# MCP23017_I8O4_v1_1.net
KiCad netlist of a schematic drawn in EAGLE
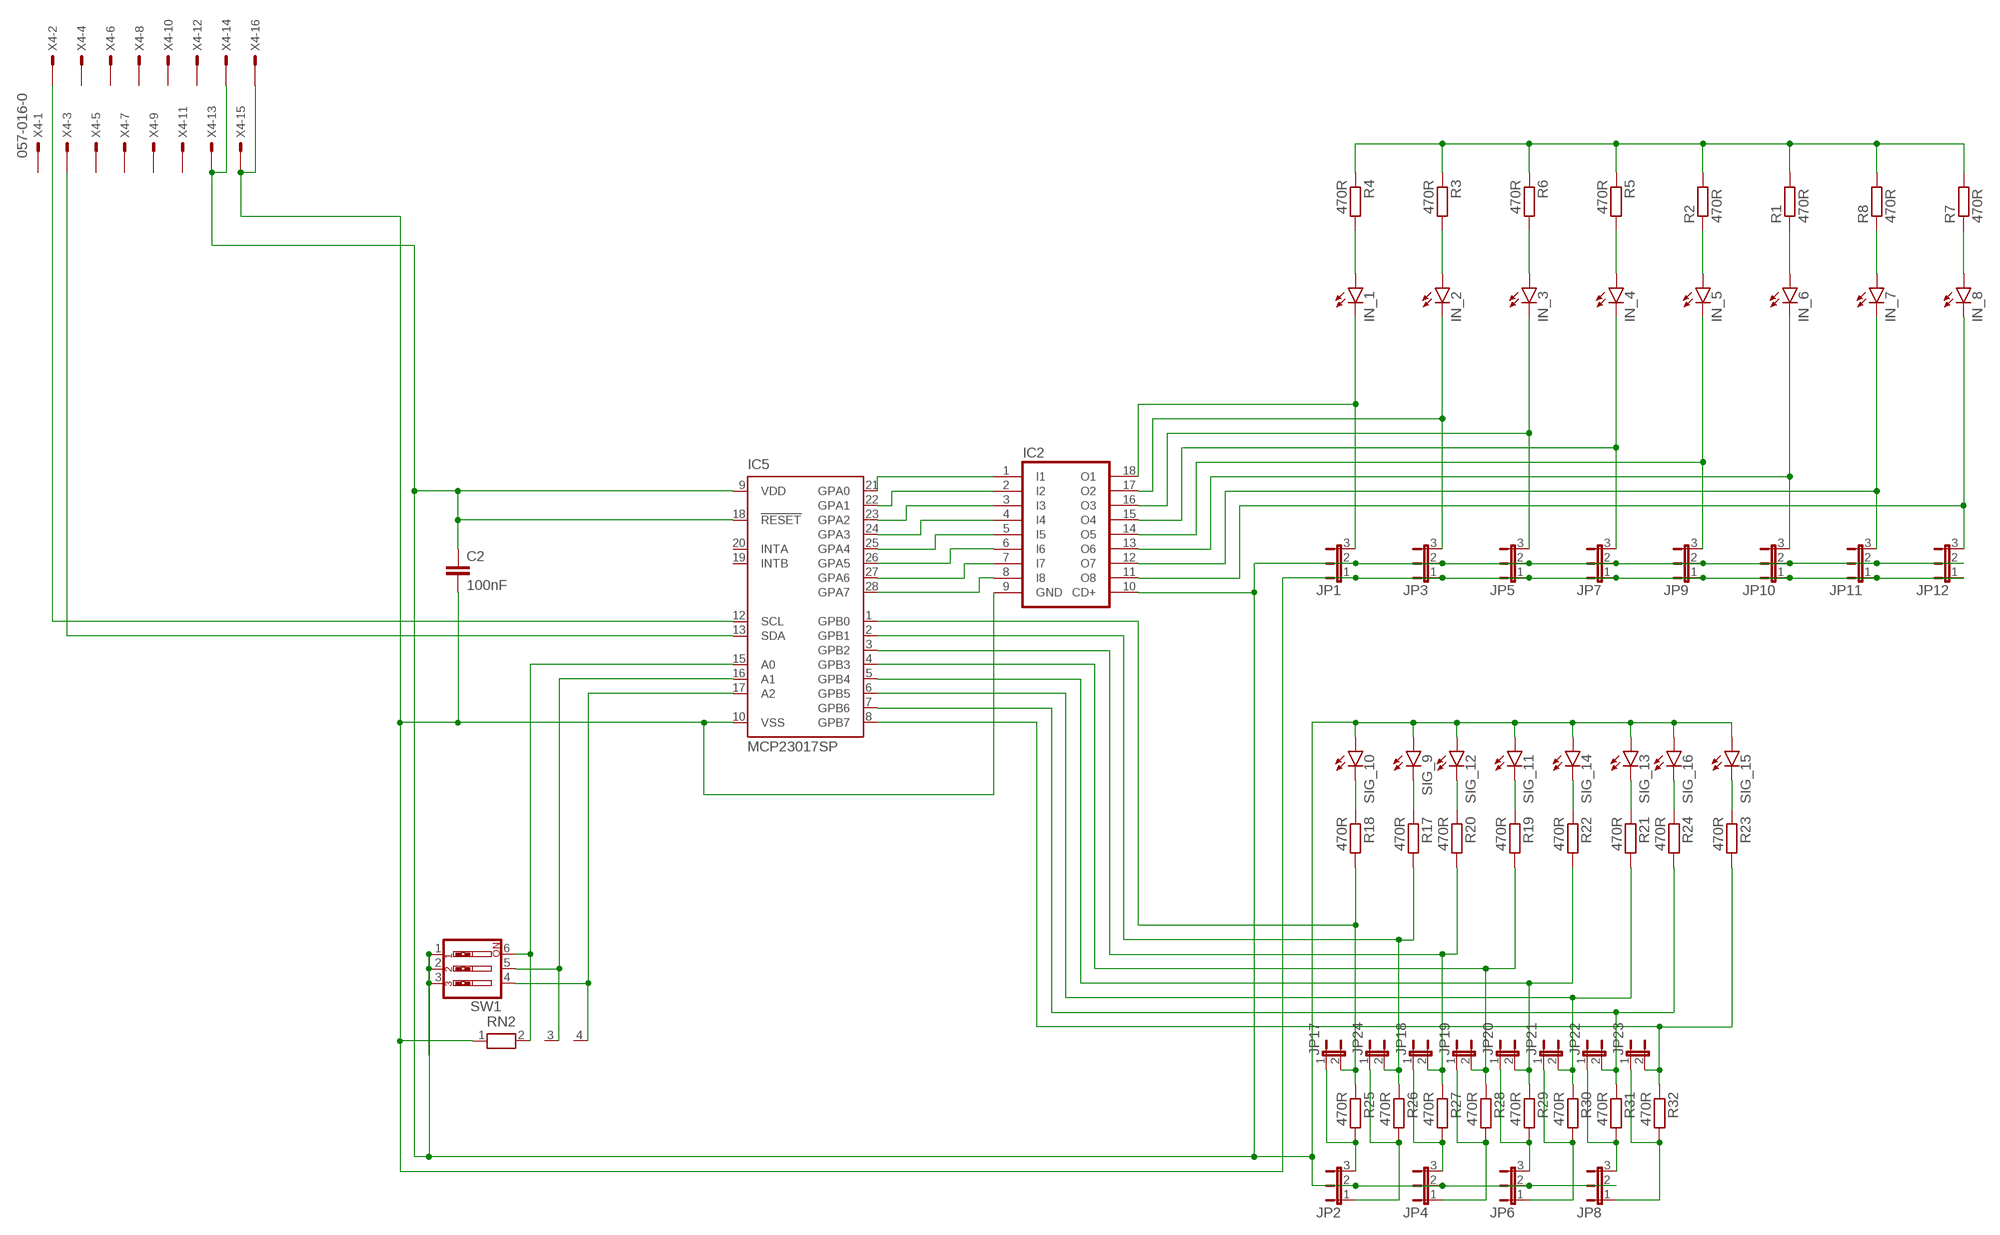
[diagram p0: schematic, sheet 1]

(export (version "E")
  (design (tool "Eeschema 10.0.6"))
  (components
    (comp (ref "C2")
      (value "100nF")
      (footprint "eagle-import:C025-024X044")
      (libsource (lib "eagle-import") (part "C-EU025-024X044"))
    )
    (comp (ref "IC2")
      (value "ULN2803A")
      (footprint "eagle-import:DIL18")
      (libsource (lib "eagle-import") (part "ULN2803A"))
    )
    (comp (ref "IC5")
      (value "MCP23017SP")
      (footprint "eagle-import:DIL28-3")
      (libsource (lib "eagle-import") (part "MCP23017SP"))
    )
    (comp (ref "IN_1")
      (value "LED3MM")
      (footprint "eagle-import:LED3MM")
      (libsource (lib "eagle-import") (part "LED3MM"))
    )
    (comp (ref "IN_2")
      (value "LED3MM")
      (footprint "eagle-import:LED3MM")
      (libsource (lib "eagle-import") (part "LED3MM"))
    )
    (comp (ref "IN_3")
      (value "LED3MM")
      (footprint "eagle-import:LED3MM")
      (libsource (lib "eagle-import") (part "LED3MM"))
    )
    (comp (ref "IN_4")
      (value "LED3MM")
      (footprint "eagle-import:LED3MM")
      (libsource (lib "eagle-import") (part "LED3MM"))
    )
    (comp (ref "IN_5")
      (value "LED3MM")
      (footprint "eagle-import:LED3MM")
      (libsource (lib "eagle-import") (part "LED3MM"))
    )
    (comp (ref "IN_6")
      (value "LED3MM")
      (footprint "eagle-import:LED3MM")
      (libsource (lib "eagle-import") (part "LED3MM"))
    )
    (comp (ref "IN_7")
      (value "LED3MM")
      (footprint "eagle-import:LED3MM")
      (libsource (lib "eagle-import") (part "LED3MM"))
    )
    (comp (ref "IN_8")
      (value "LED3MM")
      (footprint "eagle-import:LED3MM")
      (libsource (lib "eagle-import") (part "LED3MM"))
    )
    (comp (ref "JP1")
      (value "JP2E")
      (footprint "eagle-import:JP2")
      (libsource (lib "eagle-import") (part "JP2E"))
    )
    (comp (ref "JP2")
      (value "JP2E")
      (footprint "eagle-import:JP2")
      (libsource (lib "eagle-import") (part "JP2E"))
    )
    (comp (ref "JP3")
      (value "JP2E")
      (footprint "eagle-import:JP2")
      (libsource (lib "eagle-import") (part "JP2E"))
    )
    (comp (ref "JP4")
      (value "JP2E")
      (footprint "eagle-import:JP2")
      (libsource (lib "eagle-import") (part "JP2E"))
    )
    (comp (ref "JP5")
      (value "JP2E")
      (footprint "eagle-import:JP2")
      (libsource (lib "eagle-import") (part "JP2E"))
    )
    (comp (ref "JP6")
      (value "JP2E")
      (footprint "eagle-import:JP2")
      (libsource (lib "eagle-import") (part "JP2E"))
    )
    (comp (ref "JP7")
      (value "JP2E")
      (footprint "eagle-import:JP2")
      (libsource (lib "eagle-import") (part "JP2E"))
    )
    (comp (ref "JP8")
      (value "JP2E")
      (footprint "eagle-import:JP2")
      (libsource (lib "eagle-import") (part "JP2E"))
    )
    (comp (ref "JP9")
      (value "JP2E")
      (footprint "eagle-import:JP2")
      (libsource (lib "eagle-import") (part "JP2E"))
    )
    (comp (ref "JP10")
      (value "JP2E")
      (footprint "eagle-import:JP2")
      (libsource (lib "eagle-import") (part "JP2E"))
    )
    (comp (ref "JP11")
      (value "JP2E")
      (footprint "eagle-import:JP2")
      (libsource (lib "eagle-import") (part "JP2E"))
    )
    (comp (ref "JP12")
      (value "JP2E")
      (footprint "eagle-import:JP2")
      (libsource (lib "eagle-import") (part "JP2E"))
    )
    (comp (ref "JP17")
      (value "JP1E")
      (footprint "eagle-import:JP1")
      (libsource (lib "eagle-import") (part "JP1E"))
    )
    (comp (ref "JP18")
      (value "JP1E")
      (footprint "eagle-import:JP1")
      (libsource (lib "eagle-import") (part "JP1E"))
    )
    (comp (ref "JP19")
      (value "JP1E")
      (footprint "eagle-import:JP1")
      (libsource (lib "eagle-import") (part "JP1E"))
    )
    (comp (ref "JP20")
      (value "JP1E")
      (footprint "eagle-import:JP1")
      (libsource (lib "eagle-import") (part "JP1E"))
    )
    (comp (ref "JP21")
      (value "JP1E")
      (footprint "eagle-import:JP1")
      (libsource (lib "eagle-import") (part "JP1E"))
    )
    (comp (ref "JP22")
      (value "JP1E")
      (footprint "eagle-import:JP1")
      (libsource (lib "eagle-import") (part "JP1E"))
    )
    (comp (ref "JP23")
      (value "JP1E")
      (footprint "eagle-import:JP1")
      (libsource (lib "eagle-import") (part "JP1E"))
    )
    (comp (ref "JP24")
      (value "JP1E")
      (footprint "eagle-import:JP1")
      (libsource (lib "eagle-import") (part "JP1E"))
    )
    (comp (ref "R1")
      (value "470R")
      (footprint "eagle-import:0309_10")
      (libsource (lib "eagle-import") (part "R-EU_0309/10"))
    )
    (comp (ref "R2")
      (value "470R")
      (footprint "eagle-import:0309_10")
      (libsource (lib "eagle-import") (part "R-EU_0309/10"))
    )
    (comp (ref "R3")
      (value "470R")
      (footprint "eagle-import:0309_10")
      (libsource (lib "eagle-import") (part "R-EU_0309/10"))
    )
    (comp (ref "R4")
      (value "470R")
      (footprint "eagle-import:0309_10")
      (libsource (lib "eagle-import") (part "R-EU_0309/10"))
    )
    (comp (ref "R5")
      (value "470R")
      (footprint "eagle-import:0309_10")
      (libsource (lib "eagle-import") (part "R-EU_0309/10"))
    )
    (comp (ref "R6")
      (value "470R")
      (footprint "eagle-import:0309_10")
      (libsource (lib "eagle-import") (part "R-EU_0309/10"))
    )
    (comp (ref "R7")
      (value "470R")
      (footprint "eagle-import:0309_10")
      (libsource (lib "eagle-import") (part "R-EU_0309/10"))
    )
    (comp (ref "R8")
      (value "470R")
      (footprint "eagle-import:0309_10")
      (libsource (lib "eagle-import") (part "R-EU_0309/10"))
    )
    (comp (ref "R17")
      (value "470R")
      (footprint "eagle-import:0309_10")
      (libsource (lib "eagle-import") (part "R-EU_0309/10"))
    )
    (comp (ref "R18")
      (value "470R")
      (footprint "eagle-import:0309_10")
      (libsource (lib "eagle-import") (part "R-EU_0309/10"))
    )
    (comp (ref "R19")
      (value "470R")
      (footprint "eagle-import:0309_10")
      (libsource (lib "eagle-import") (part "R-EU_0309/10"))
    )
    (comp (ref "R20")
      (value "470R")
      (footprint "eagle-import:0309_10")
      (libsource (lib "eagle-import") (part "R-EU_0309/10"))
    )
    (comp (ref "R21")
      (value "470R")
      (footprint "eagle-import:0309_10")
      (libsource (lib "eagle-import") (part "R-EU_0309/10"))
    )
    (comp (ref "R22")
      (value "470R")
      (footprint "eagle-import:0309_10")
      (libsource (lib "eagle-import") (part "R-EU_0309/10"))
    )
    (comp (ref "R23")
      (value "470R")
      (footprint "eagle-import:0309_10")
      (libsource (lib "eagle-import") (part "R-EU_0309/10"))
    )
    (comp (ref "R24")
      (value "470R")
      (footprint "eagle-import:0309_10")
      (libsource (lib "eagle-import") (part "R-EU_0309/10"))
    )
    (comp (ref "R25")
      (value "470R")
      (footprint "eagle-import:0309_10")
      (libsource (lib "eagle-import") (part "R-EU_0309/10"))
    )
    (comp (ref "R26")
      (value "470R")
      (footprint "eagle-import:0309_10")
      (libsource (lib "eagle-import") (part "R-EU_0309/10"))
    )
    (comp (ref "R27")
      (value "470R")
      (footprint "eagle-import:0309_10")
      (libsource (lib "eagle-import") (part "R-EU_0309/10"))
    )
    (comp (ref "R28")
      (value "470R")
      (footprint "eagle-import:0309_10")
      (libsource (lib "eagle-import") (part "R-EU_0309/10"))
    )
    (comp (ref "R29")
      (value "470R")
      (footprint "eagle-import:0309_10")
      (libsource (lib "eagle-import") (part "R-EU_0309/10"))
    )
    (comp (ref "R30")
      (value "470R")
      (footprint "eagle-import:0309_10")
      (libsource (lib "eagle-import") (part "R-EU_0309/10"))
    )
    (comp (ref "R31")
      (value "470R")
      (footprint "eagle-import:0309_10")
      (libsource (lib "eagle-import") (part "R-EU_0309/10"))
    )
    (comp (ref "R32")
      (value "470R")
      (footprint "eagle-import:0309_10")
      (libsource (lib "eagle-import") (part "R-EU_0309/10"))
    )
    (comp (ref "RN2")
      (value "RN03")
      (footprint "eagle-import:RN-3")
      (libsource (lib "eagle-import") (part "RN03"))
    )
    (comp (ref "SIG_9")
      (value "LED3MM")
      (footprint "eagle-import:LED3MM")
      (libsource (lib "eagle-import") (part "LED3MM"))
    )
    (comp (ref "SIG_10")
      (value "LED3MM")
      (footprint "eagle-import:LED3MM")
      (libsource (lib "eagle-import") (part "LED3MM"))
    )
    (comp (ref "SIG_11")
      (value "LED3MM")
      (footprint "eagle-import:LED3MM")
      (libsource (lib "eagle-import") (part "LED3MM"))
    )
    (comp (ref "SIG_12")
      (value "LED3MM")
      (footprint "eagle-import:LED3MM")
      (libsource (lib "eagle-import") (part "LED3MM"))
    )
    (comp (ref "SIG_13")
      (value "LED3MM")
      (footprint "eagle-import:LED3MM")
      (libsource (lib "eagle-import") (part "LED3MM"))
    )
    (comp (ref "SIG_14")
      (value "LED3MM")
      (footprint "eagle-import:LED3MM")
      (libsource (lib "eagle-import") (part "LED3MM"))
    )
    (comp (ref "SIG_15")
      (value "LED3MM")
      (footprint "eagle-import:LED3MM")
      (libsource (lib "eagle-import") (part "LED3MM"))
    )
    (comp (ref "SIG_16")
      (value "LED3MM")
      (footprint "eagle-import:LED3MM")
      (libsource (lib "eagle-import") (part "LED3MM"))
    )
    (comp (ref "SW1")
      (value "SW_DIP-3")
      (footprint "eagle-import:EDG-03")
      (libsource (lib "eagle-import") (part "SW_DIP-3"))
    )
    (comp (ref "X4")
      (value "057-016-0")
      (footprint "eagle-import:057-016-0")
      (libsource (lib "eagle-import") (part "057-016-0"))
    )
  )
  (nets
    (net (code "1") (name "Net-(IC2-CD+)") (class "Default")
      (node (ref "C2") (pin "1") (pinfunction "1_1") (pintype "passive"))
      (node (ref "IC2") (pin "10") (pinfunction "CD+_10") (pintype "passive"))
      (node (ref "IC5") (pin "18") (pinfunction "~{RESET}_18") (pintype "input"))
      (node (ref "IC5") (pin "9") (pinfunction "VDD_9") (pintype "power_in"))
      (node (ref "JP1") (pin "2") (pinfunction "2_2") (pintype "passive"))
      (node (ref "JP10") (pin "2") (pinfunction "2_2") (pintype "passive"))
      (node (ref "JP11") (pin "2") (pinfunction "2_2") (pintype "passive"))
      (node (ref "JP12") (pin "2") (pinfunction "2_2") (pintype "passive"))
      (node (ref "JP2") (pin "2") (pinfunction "2_2") (pintype "passive"))
      (node (ref "JP3") (pin "2") (pinfunction "2_2") (pintype "passive"))
      (node (ref "JP4") (pin "2") (pinfunction "2_2") (pintype "passive"))
      (node (ref "JP5") (pin "2") (pinfunction "2_2") (pintype "passive"))
      (node (ref "JP6") (pin "2") (pinfunction "2_2") (pintype "passive"))
      (node (ref "JP7") (pin "2") (pinfunction "2_2") (pintype "passive"))
      (node (ref "JP8") (pin "2") (pinfunction "2_2") (pintype "passive"))
      (node (ref "JP9") (pin "2") (pinfunction "2_2") (pintype "passive"))
      (node (ref "SIG_10") (pin "A") (pinfunction "A_A") (pintype "passive"))
      (node (ref "SIG_11") (pin "A") (pinfunction "A_A") (pintype "passive"))
      (node (ref "SIG_12") (pin "A") (pinfunction "A_A") (pintype "passive"))
      (node (ref "SIG_13") (pin "A") (pinfunction "A_A") (pintype "passive"))
      (node (ref "SIG_14") (pin "A") (pinfunction "A_A") (pintype "passive"))
      (node (ref "SIG_15") (pin "A") (pinfunction "A_A") (pintype "passive"))
      (node (ref "SIG_16") (pin "A") (pinfunction "A_A") (pintype "passive"))
      (node (ref "SIG_9") (pin "A") (pinfunction "A_A") (pintype "passive"))
      (node (ref "SW1") (pin "1") (pinfunction "1_1") (pintype "passive"))
      (node (ref "SW1") (pin "2") (pinfunction "2_2") (pintype "passive"))
      (node (ref "SW1") (pin "3") (pinfunction "3_3") (pintype "passive"))
      (node (ref "X4") (pin "13") (pinfunction "S_13") (pintype "passive"))
      (node (ref "X4") (pin "14") (pinfunction "S_14") (pintype "passive"))
    )
    (net (code "2") (name "Net-(IC2-GND)") (class "Default")
      (node (ref "C2") (pin "2") (pinfunction "2_2") (pintype "passive"))
      (node (ref "IC2") (pin "9") (pinfunction "GND_9") (pintype "power_in"))
      (node (ref "IC5") (pin "10") (pinfunction "VSS_10") (pintype "power_in"))
      (node (ref "JP1") (pin "1") (pinfunction "1_1") (pintype "passive"))
      (node (ref "JP10") (pin "1") (pinfunction "1_1") (pintype "passive"))
      (node (ref "JP11") (pin "1") (pinfunction "1_1") (pintype "passive"))
      (node (ref "JP12") (pin "1") (pinfunction "1_1") (pintype "passive"))
      (node (ref "JP3") (pin "1") (pinfunction "1_1") (pintype "passive"))
      (node (ref "JP5") (pin "1") (pinfunction "1_1") (pintype "passive"))
      (node (ref "JP7") (pin "1") (pinfunction "1_1") (pintype "passive"))
      (node (ref "JP9") (pin "1") (pinfunction "1_1") (pintype "passive"))
      (node (ref "RN2") (pin "1") (pinfunction "1_1") (pintype "passive"))
      (node (ref "X4") (pin "15") (pinfunction "S_15") (pintype "passive"))
      (node (ref "X4") (pin "16") (pinfunction "S_16") (pintype "passive"))
    )
    (net (code "3") (name "Net-(IC2-I1)") (class "Default")
      (node (ref "IC2") (pin "1") (pinfunction "I1_1") (pintype "input"))
      (node (ref "IC5") (pin "21") (pinfunction "GPA0_21") (pintype "bidirectional"))
    )
    (net (code "4") (name "Net-(IC2-I2)") (class "Default")
      (node (ref "IC2") (pin "2") (pinfunction "I2_2") (pintype "input"))
      (node (ref "IC5") (pin "22") (pinfunction "GPA1_22") (pintype "bidirectional"))
    )
    (net (code "5") (name "Net-(IC2-I3)") (class "Default")
      (node (ref "IC2") (pin "3") (pinfunction "I3_3") (pintype "input"))
      (node (ref "IC5") (pin "23") (pinfunction "GPA2_23") (pintype "bidirectional"))
    )
    (net (code "6") (name "Net-(IC2-I4)") (class "Default")
      (node (ref "IC2") (pin "4") (pinfunction "I4_4") (pintype "input"))
      (node (ref "IC5") (pin "24") (pinfunction "GPA3_24") (pintype "bidirectional"))
    )
    (net (code "7") (name "Net-(IC2-I5)") (class "Default")
      (node (ref "IC2") (pin "5") (pinfunction "I5_5") (pintype "input"))
      (node (ref "IC5") (pin "25") (pinfunction "GPA4_25") (pintype "bidirectional"))
    )
    (net (code "8") (name "Net-(IC2-I6)") (class "Default")
      (node (ref "IC2") (pin "6") (pinfunction "I6_6") (pintype "input"))
      (node (ref "IC5") (pin "26") (pinfunction "GPA5_26") (pintype "bidirectional"))
    )
    (net (code "9") (name "Net-(IC2-I7)") (class "Default")
      (node (ref "IC2") (pin "7") (pinfunction "I7_7") (pintype "input"))
      (node (ref "IC5") (pin "27") (pinfunction "GPA6_27") (pintype "bidirectional"))
    )
    (net (code "10") (name "Net-(IC2-I8)") (class "Default")
      (node (ref "IC2") (pin "8") (pinfunction "I8_8") (pintype "input"))
      (node (ref "IC5") (pin "28") (pinfunction "GPA7_28") (pintype "bidirectional"))
    )
    (net (code "11") (name "Net-(IC2-O1)") (class "Default")
      (node (ref "IC2") (pin "18") (pinfunction "O1_18") (pintype "open_collector"))
      (node (ref "IN_1") (pin "K") (pinfunction "C_K") (pintype "passive"))
      (node (ref "JP1") (pin "3") (pinfunction "3_3") (pintype "passive"))
    )
    (net (code "12") (name "Net-(IC2-O2)") (class "Default")
      (node (ref "IC2") (pin "17") (pinfunction "O2_17") (pintype "open_collector"))
      (node (ref "IN_2") (pin "K") (pinfunction "C_K") (pintype "passive"))
      (node (ref "JP3") (pin "3") (pinfunction "3_3") (pintype "passive"))
    )
    (net (code "13") (name "Net-(IC2-O3)") (class "Default")
      (node (ref "IC2") (pin "16") (pinfunction "O3_16") (pintype "open_collector"))
      (node (ref "IN_3") (pin "K") (pinfunction "C_K") (pintype "passive"))
      (node (ref "JP5") (pin "3") (pinfunction "3_3") (pintype "passive"))
    )
    (net (code "14") (name "Net-(IC2-O4)") (class "Default")
      (node (ref "IC2") (pin "15") (pinfunction "O4_15") (pintype "open_collector"))
      (node (ref "IN_4") (pin "K") (pinfunction "C_K") (pintype "passive"))
      (node (ref "JP7") (pin "3") (pinfunction "3_3") (pintype "passive"))
    )
    (net (code "15") (name "Net-(IC2-O5)") (class "Default")
      (node (ref "IC2") (pin "14") (pinfunction "O5_14") (pintype "open_collector"))
      (node (ref "IN_5") (pin "K") (pinfunction "C_K") (pintype "passive"))
      (node (ref "JP9") (pin "3") (pinfunction "3_3") (pintype "passive"))
    )
    (net (code "16") (name "Net-(IC2-O6)") (class "Default")
      (node (ref "IC2") (pin "13") (pinfunction "O6_13") (pintype "open_collector"))
      (node (ref "IN_6") (pin "K") (pinfunction "C_K") (pintype "passive"))
      (node (ref "JP10") (pin "3") (pinfunction "3_3") (pintype "passive"))
    )
    (net (code "17") (name "Net-(IC2-O7)") (class "Default")
      (node (ref "IC2") (pin "12") (pinfunction "O7_12") (pintype "open_collector"))
      (node (ref "IN_7") (pin "K") (pinfunction "C_K") (pintype "passive"))
      (node (ref "JP11") (pin "3") (pinfunction "3_3") (pintype "passive"))
    )
    (net (code "18") (name "Net-(IC2-O8)") (class "Default")
      (node (ref "IC2") (pin "11") (pinfunction "O8_11") (pintype "open_collector"))
      (node (ref "IN_8") (pin "K") (pinfunction "C_K") (pintype "passive"))
      (node (ref "JP12") (pin "3") (pinfunction "3_3") (pintype "passive"))
    )
    (net (code "19") (name "Net-(IC5-A0)") (class "Default")
      (node (ref "IC5") (pin "15") (pinfunction "A0_15") (pintype "input"))
      (node (ref "RN2") (pin "2") (pinfunction "2_2") (pintype "passive"))
      (node (ref "SW1") (pin "6") (pinfunction "6_6") (pintype "passive"))
    )
    (net (code "20") (name "Net-(IC5-A1)") (class "Default")
      (node (ref "IC5") (pin "16") (pinfunction "A1_16") (pintype "input"))
      (node (ref "RN2") (pin "3") (pinfunction "3_3") (pintype "passive"))
      (node (ref "SW1") (pin "5") (pinfunction "5_5") (pintype "passive"))
    )
    (net (code "21") (name "Net-(IC5-A2)") (class "Default")
      (node (ref "IC5") (pin "17") (pinfunction "A2_17") (pintype "input"))
      (node (ref "RN2") (pin "4") (pinfunction "4_4") (pintype "passive"))
      (node (ref "SW1") (pin "4") (pinfunction "4_4") (pintype "passive"))
    )
    (net (code "22") (name "Net-(IC5-GPB0)") (class "Default")
      (node (ref "IC5") (pin "1") (pinfunction "GPB0_1") (pintype "bidirectional"))
      (node (ref "JP17") (pin "2") (pinfunction "2_2") (pintype "passive"))
      (node (ref "R18") (pin "2") (pinfunction "2_2") (pintype "passive"))
      (node (ref "R25") (pin "1") (pinfunction "1_1") (pintype "passive"))
    )
    (net (code "23") (name "Net-(IC5-GPB1)") (class "Default")
      (node (ref "IC5") (pin "2") (pinfunction "GPB1_2") (pintype "bidirectional"))
      (node (ref "JP24") (pin "2") (pinfunction "2_2") (pintype "passive"))
      (node (ref "R17") (pin "2") (pinfunction "2_2") (pintype "passive"))
      (node (ref "R26") (pin "1") (pinfunction "1_1") (pintype "passive"))
    )
    (net (code "24") (name "Net-(IC5-GPB2)") (class "Default")
      (node (ref "IC5") (pin "3") (pinfunction "GPB2_3") (pintype "bidirectional"))
      (node (ref "JP18") (pin "2") (pinfunction "2_2") (pintype "passive"))
      (node (ref "R20") (pin "2") (pinfunction "2_2") (pintype "passive"))
      (node (ref "R27") (pin "1") (pinfunction "1_1") (pintype "passive"))
    )
    (net (code "25") (name "Net-(IC5-GPB3)") (class "Default")
      (node (ref "IC5") (pin "4") (pinfunction "GPB3_4") (pintype "bidirectional"))
      (node (ref "JP19") (pin "2") (pinfunction "2_2") (pintype "passive"))
      (node (ref "R19") (pin "2") (pinfunction "2_2") (pintype "passive"))
      (node (ref "R28") (pin "1") (pinfunction "1_1") (pintype "passive"))
    )
    (net (code "26") (name "Net-(IC5-GPB4)") (class "Default")
      (node (ref "IC5") (pin "5") (pinfunction "GPB4_5") (pintype "bidirectional"))
      (node (ref "JP20") (pin "2") (pinfunction "2_2") (pintype "passive"))
      (node (ref "R22") (pin "2") (pinfunction "2_2") (pintype "passive"))
      (node (ref "R29") (pin "1") (pinfunction "1_1") (pintype "passive"))
    )
    (net (code "27") (name "Net-(IC5-GPB5)") (class "Default")
      (node (ref "IC5") (pin "6") (pinfunction "GPB5_6") (pintype "bidirectional"))
      (node (ref "JP21") (pin "2") (pinfunction "2_2") (pintype "passive"))
      (node (ref "R21") (pin "2") (pinfunction "2_2") (pintype "passive"))
      (node (ref "R30") (pin "1") (pinfunction "1_1") (pintype "passive"))
    )
    (net (code "28") (name "Net-(IC5-GPB6)") (class "Default")
      (node (ref "IC5") (pin "7") (pinfunction "GPB6_7") (pintype "bidirectional"))
      (node (ref "JP22") (pin "2") (pinfunction "2_2") (pintype "passive"))
      (node (ref "R24") (pin "2") (pinfunction "2_2") (pintype "passive"))
      (node (ref "R31") (pin "1") (pinfunction "1_1") (pintype "passive"))
    )
    (net (code "29") (name "Net-(IC5-GPB7)") (class "Default")
      (node (ref "IC5") (pin "8") (pinfunction "GPB7_8") (pintype "bidirectional"))
      (node (ref "JP23") (pin "2") (pinfunction "2_2") (pintype "passive"))
      (node (ref "R23") (pin "2") (pinfunction "2_2") (pintype "passive"))
      (node (ref "R32") (pin "1") (pinfunction "1_1") (pintype "passive"))
    )
    (net (code "30") (name "Net-(IC5-SCL)") (class "Default")
      (node (ref "IC5") (pin "12") (pinfunction "SCL_12") (pintype "input"))
      (node (ref "X4") (pin "2") (pinfunction "S_2") (pintype "passive"))
    )
    (net (code "31") (name "Net-(IC5-SDA)") (class "Default")
      (node (ref "IC5") (pin "13") (pinfunction "SDA_13") (pintype "bidirectional"))
      (node (ref "X4") (pin "3") (pinfunction "S_3") (pintype "passive"))
    )
    (net (code "32") (name "Net-(IN_1-PadA)") (class "Default")
      (node (ref "IN_1") (pin "A") (pinfunction "A_A") (pintype "passive"))
      (node (ref "R4") (pin "2") (pinfunction "2_2") (pintype "passive"))
    )
    (net (code "33") (name "Net-(IN_2-PadA)") (class "Default")
      (node (ref "IN_2") (pin "A") (pinfunction "A_A") (pintype "passive"))
      (node (ref "R3") (pin "2") (pinfunction "2_2") (pintype "passive"))
    )
    (net (code "34") (name "Net-(IN_3-PadA)") (class "Default")
      (node (ref "IN_3") (pin "A") (pinfunction "A_A") (pintype "passive"))
      (node (ref "R6") (pin "2") (pinfunction "2_2") (pintype "passive"))
    )
    (net (code "35") (name "Net-(IN_4-PadA)") (class "Default")
      (node (ref "IN_4") (pin "A") (pinfunction "A_A") (pintype "passive"))
      (node (ref "R5") (pin "2") (pinfunction "2_2") (pintype "passive"))
    )
    (net (code "36") (name "Net-(IN_5-PadA)") (class "Default")
      (node (ref "IN_5") (pin "A") (pinfunction "A_A") (pintype "passive"))
      (node (ref "R2") (pin "1") (pinfunction "1_1") (pintype "passive"))
    )
    (net (code "37") (name "Net-(IN_6-PadA)") (class "Default")
      (node (ref "IN_6") (pin "A") (pinfunction "A_A") (pintype "passive"))
      (node (ref "R1") (pin "1") (pinfunction "1_1") (pintype "passive"))
    )
    (net (code "38") (name "Net-(IN_7-PadA)") (class "Default")
      (node (ref "IN_7") (pin "A") (pinfunction "A_A") (pintype "passive"))
      (node (ref "R8") (pin "1") (pinfunction "1_1") (pintype "passive"))
    )
    (net (code "39") (name "Net-(IN_8-PadA)") (class "Default")
      (node (ref "IN_8") (pin "A") (pinfunction "A_A") (pintype "passive"))
      (node (ref "R7") (pin "1") (pinfunction "1_1") (pintype "passive"))
    )
    (net (code "40") (name "Net-(JP2-Pad1)") (class "Default")
      (node (ref "JP2") (pin "1") (pinfunction "1_1") (pintype "passive"))
      (node (ref "JP24") (pin "1") (pinfunction "1_1") (pintype "passive"))
      (node (ref "R26") (pin "2") (pinfunction "2_2") (pintype "passive"))
    )
    (net (code "41") (name "Net-(JP17-Pad1)") (class "Default")
      (node (ref "JP17") (pin "1") (pinfunction "1_1") (pintype "passive"))
      (node (ref "JP2") (pin "3") (pinfunction "3_3") (pintype "passive"))
      (node (ref "R25") (pin "2") (pinfunction "2_2") (pintype "passive"))
    )
    (net (code "42") (name "Net-(JP18-Pad1)") (class "Default")
      (node (ref "JP18") (pin "1") (pinfunction "1_1") (pintype "passive"))
      (node (ref "JP4") (pin "3") (pinfunction "3_3") (pintype "passive"))
      (node (ref "R27") (pin "2") (pinfunction "2_2") (pintype "passive"))
    )
    (net (code "43") (name "Net-(JP19-Pad1)") (class "Default")
      (node (ref "JP19") (pin "1") (pinfunction "1_1") (pintype "passive"))
      (node (ref "JP4") (pin "1") (pinfunction "1_1") (pintype "passive"))
      (node (ref "R28") (pin "2") (pinfunction "2_2") (pintype "passive"))
    )
    (net (code "44") (name "Net-(JP20-Pad1)") (class "Default")
      (node (ref "JP20") (pin "1") (pinfunction "1_1") (pintype "passive"))
      (node (ref "JP6") (pin "3") (pinfunction "3_3") (pintype "passive"))
      (node (ref "R29") (pin "2") (pinfunction "2_2") (pintype "passive"))
    )
    (net (code "45") (name "Net-(JP21-Pad1)") (class "Default")
      (node (ref "JP21") (pin "1") (pinfunction "1_1") (pintype "passive"))
      (node (ref "JP6") (pin "1") (pinfunction "1_1") (pintype "passive"))
      (node (ref "R30") (pin "2") (pinfunction "2_2") (pintype "passive"))
    )
    (net (code "46") (name "Net-(JP22-Pad1)") (class "Default")
      (node (ref "JP22") (pin "1") (pinfunction "1_1") (pintype "passive"))
      (node (ref "JP8") (pin "3") (pinfunction "3_3") (pintype "passive"))
      (node (ref "R31") (pin "2") (pinfunction "2_2") (pintype "passive"))
    )
    (net (code "47") (name "Net-(JP23-Pad1)") (class "Default")
      (node (ref "JP23") (pin "1") (pinfunction "1_1") (pintype "passive"))
      (node (ref "JP8") (pin "1") (pinfunction "1_1") (pintype "passive"))
      (node (ref "R32") (pin "2") (pinfunction "2_2") (pintype "passive"))
    )
    (net (code "48") (name "Net-(R1-Pad2)") (class "Default")
      (node (ref "R1") (pin "2") (pinfunction "2_2") (pintype "passive"))
      (node (ref "R2") (pin "2") (pinfunction "2_2") (pintype "passive"))
      (node (ref "R3") (pin "1") (pinfunction "1_1") (pintype "passive"))
      (node (ref "R4") (pin "1") (pinfunction "1_1") (pintype "passive"))
      (node (ref "R5") (pin "1") (pinfunction "1_1") (pintype "passive"))
      (node (ref "R6") (pin "1") (pinfunction "1_1") (pintype "passive"))
      (node (ref "R7") (pin "2") (pinfunction "2_2") (pintype "passive"))
      (node (ref "R8") (pin "2") (pinfunction "2_2") (pintype "passive"))
    )
    (net (code "49") (name "Net-(SIG_9-C)") (class "Default")
      (node (ref "R17") (pin "1") (pinfunction "1_1") (pintype "passive"))
      (node (ref "SIG_9") (pin "K") (pinfunction "C_K") (pintype "passive"))
    )
    (net (code "50") (name "Net-(SIG_10-C)") (class "Default")
      (node (ref "R18") (pin "1") (pinfunction "1_1") (pintype "passive"))
      (node (ref "SIG_10") (pin "K") (pinfunction "C_K") (pintype "passive"))
    )
    (net (code "51") (name "Net-(SIG_11-C)") (class "Default")
      (node (ref "R19") (pin "1") (pinfunction "1_1") (pintype "passive"))
      (node (ref "SIG_11") (pin "K") (pinfunction "C_K") (pintype "passive"))
    )
    (net (code "52") (name "Net-(SIG_12-C)") (class "Default")
      (node (ref "R20") (pin "1") (pinfunction "1_1") (pintype "passive"))
      (node (ref "SIG_12") (pin "K") (pinfunction "C_K") (pintype "passive"))
    )
    (net (code "53") (name "Net-(SIG_13-C)") (class "Default")
      (node (ref "R21") (pin "1") (pinfunction "1_1") (pintype "passive"))
      (node (ref "SIG_13") (pin "K") (pinfunction "C_K") (pintype "passive"))
    )
    (net (code "54") (name "Net-(SIG_14-C)") (class "Default")
      (node (ref "R22") (pin "1") (pinfunction "1_1") (pintype "passive"))
      (node (ref "SIG_14") (pin "K") (pinfunction "C_K") (pintype "passive"))
    )
    (net (code "55") (name "Net-(SIG_15-C)") (class "Default")
      (node (ref "R23") (pin "1") (pinfunction "1_1") (pintype "passive"))
      (node (ref "SIG_15") (pin "K") (pinfunction "C_K") (pintype "passive"))
    )
    (net (code "56") (name "Net-(SIG_16-C)") (class "Default")
      (node (ref "R24") (pin "1") (pinfunction "1_1") (pintype "passive"))
      (node (ref "SIG_16") (pin "K") (pinfunction "C_K") (pintype "passive"))
    )
    (net (code "57") (name "unconnected-(IC5-INTA-Pad20)") (class "Default")
      (node (ref "IC5") (pin "20") (pinfunction "INTA_20") (pintype "output"))
    )
    (net (code "58") (name "unconnected-(IC5-INTB-Pad19)") (class "Default")
      (node (ref "IC5") (pin "19") (pinfunction "INTB_19") (pintype "output"))
    )
    (net (code "59") (name "unconnected-(X4A-S-Pad1)") (class "Default")
      (node (ref "X4") (pin "1") (pinfunction "S_1") (pintype "passive"))
    )
    (net (code "60") (name "unconnected-(X4B-S-Pad10)") (class "Default")
      (node (ref "X4") (pin "10") (pinfunction "S_10") (pintype "passive"))
    )
    (net (code "61") (name "unconnected-(X4C-S-Pad11)") (class "Default")
      (node (ref "X4") (pin "11") (pinfunction "S_11") (pintype "passive"))
    )
    (net (code "62") (name "unconnected-(X4D-S-Pad12)") (class "Default")
      (node (ref "X4") (pin "12") (pinfunction "S_12") (pintype "passive"))
    )
    (net (code "63") (name "unconnected-(X4K-S-Pad4)") (class "Default")
      (node (ref "X4") (pin "4") (pinfunction "S_4") (pintype "passive"))
    )
    (net (code "64") (name "unconnected-(X4L-S-Pad5)") (class "Default")
      (node (ref "X4") (pin "5") (pinfunction "S_5") (pintype "passive"))
    )
    (net (code "65") (name "unconnected-(X4M-S-Pad6)") (class "Default")
      (node (ref "X4") (pin "6") (pinfunction "S_6") (pintype "passive"))
    )
    (net (code "66") (name "unconnected-(X4N-S-Pad7)") (class "Default")
      (node (ref "X4") (pin "7") (pinfunction "S_7") (pintype "passive"))
    )
    (net (code "67") (name "unconnected-(X4O-S-Pad8)") (class "Default")
      (node (ref "X4") (pin "8") (pinfunction "S_8") (pintype "passive"))
    )
    (net (code "68") (name "unconnected-(X4P-S-Pad9)") (class "Default")
      (node (ref "X4") (pin "9") (pinfunction "S_9") (pintype "passive"))
    )
  )
)
